# circle_gpio.net
KiCad netlist of a schematic drawn in EAGLE
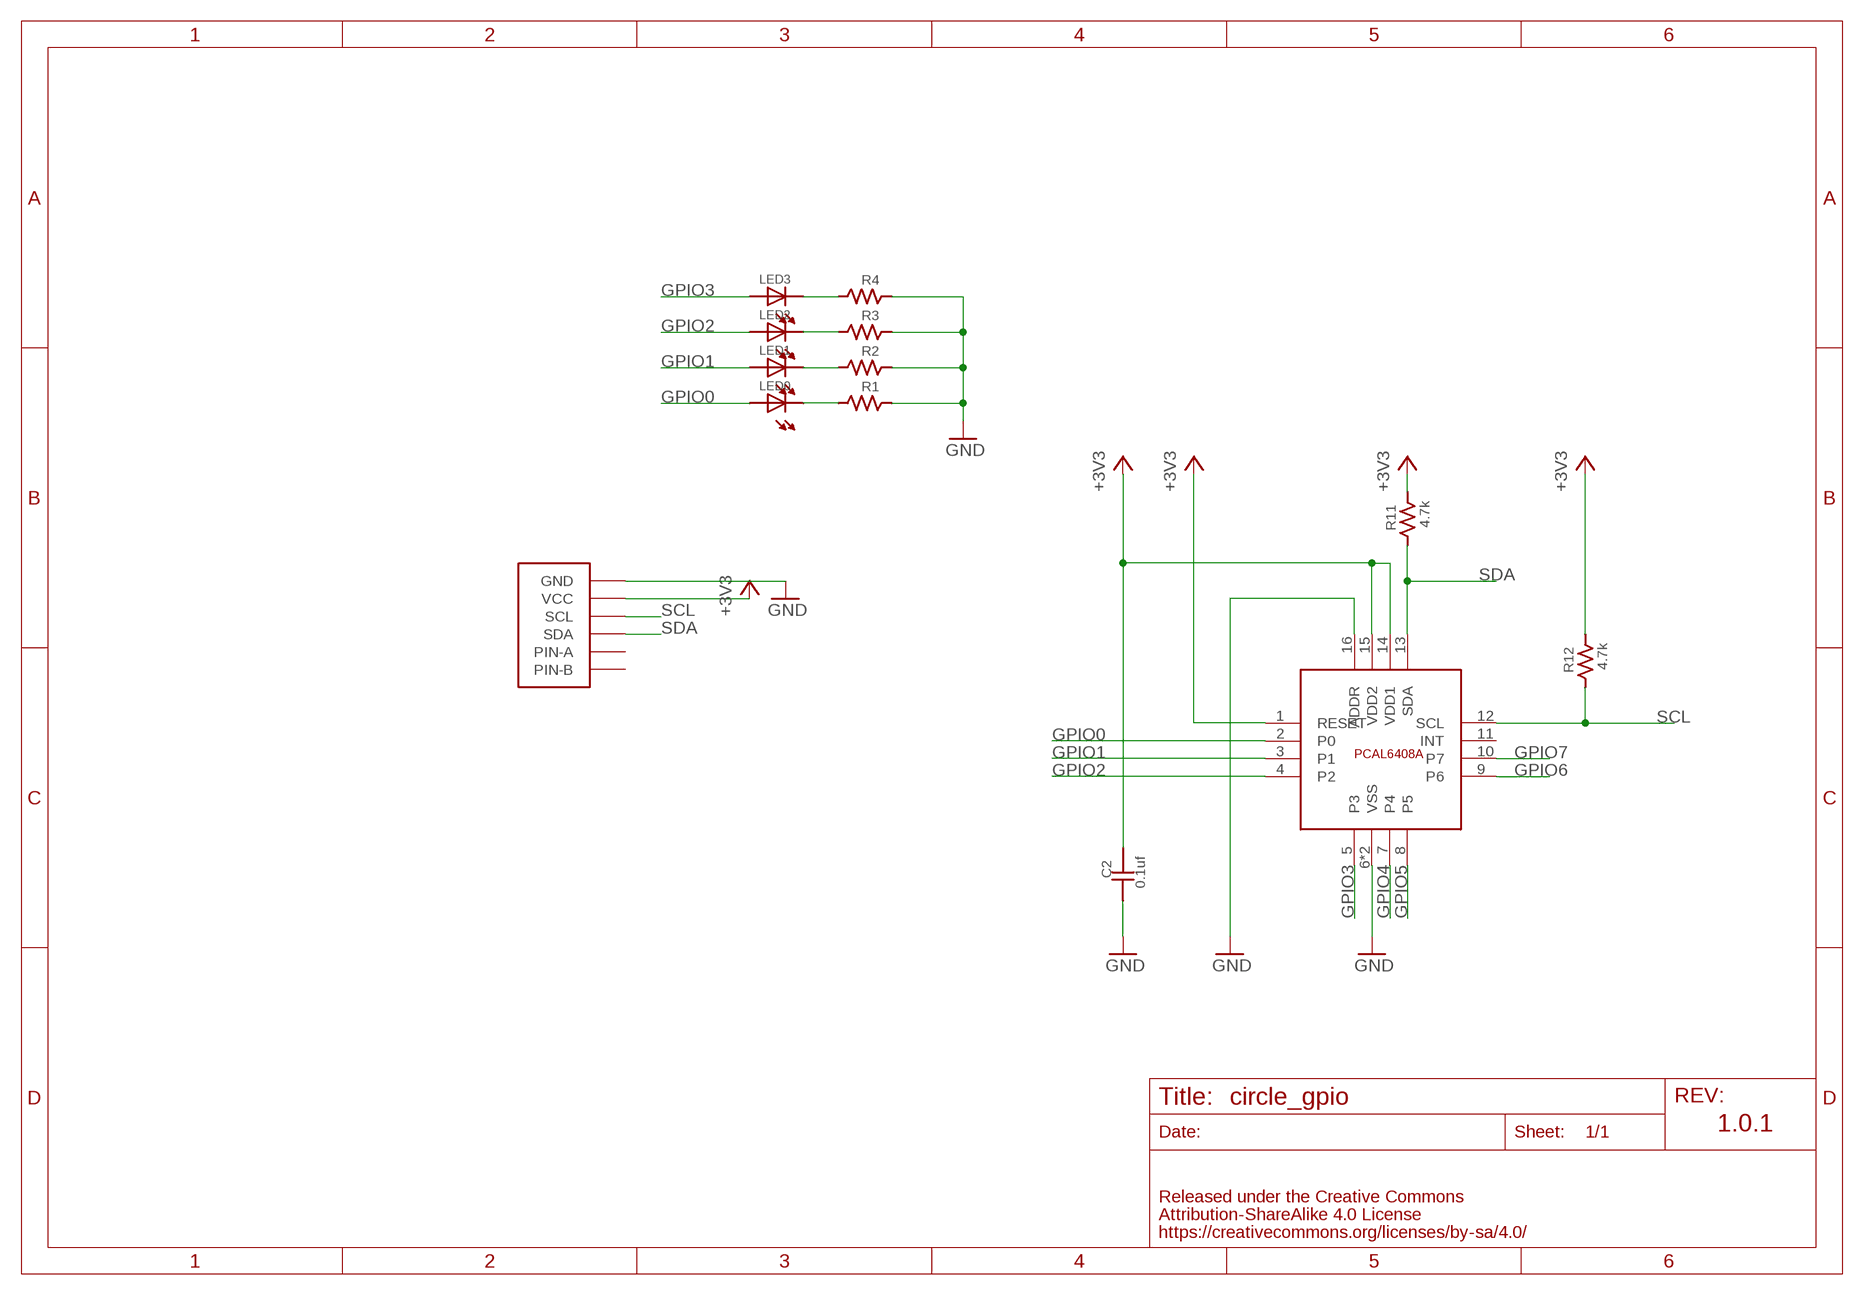
[diagram p0: schematic, sheet 1]

(export (version "E")
  (design (tool "Eeschema 10.0.6"))
  (components
    (comp (ref "C2")
      (value "0.1uf")
      (footprint "eagle-import:0402")
      (libsource (lib "eagle-import") (part "CAPACITOR0402"))
    )
    (comp (ref "LED0")
      (value "LED0402")
      (footprint "eagle-import:0402")
      (libsource (lib "eagle-import") (part "LED0402"))
    )
    (comp (ref "LED1")
      (value "LED0402")
      (footprint "eagle-import:0402")
      (libsource (lib "eagle-import") (part "LED0402"))
    )
    (comp (ref "LED2")
      (value "LED0402")
      (footprint "eagle-import:0402")
      (libsource (lib "eagle-import") (part "LED0402"))
    )
    (comp (ref "LED3")
      (value "LED0402")
      (footprint "eagle-import:0402")
      (libsource (lib "eagle-import") (part "LED0402"))
    )
    (comp (ref "R1")
      (value "RESISTOR-0402")
      (footprint "eagle-import:0402")
      (libsource (lib "eagle-import") (part "RESISTOR-0402"))
    )
    (comp (ref "R2")
      (value "RESISTOR-0402")
      (footprint "eagle-import:0402")
      (libsource (lib "eagle-import") (part "RESISTOR-0402"))
    )
    (comp (ref "R3")
      (value "RESISTOR-0402")
      (footprint "eagle-import:0402")
      (libsource (lib "eagle-import") (part "RESISTOR-0402"))
    )
    (comp (ref "R4")
      (value "RESISTOR-0402")
      (footprint "eagle-import:0402")
      (libsource (lib "eagle-import") (part "RESISTOR-0402"))
    )
    (comp (ref "R11")
      (value "4.7k")
      (footprint "eagle-import:0402")
      (libsource (lib "eagle-import") (part "RESISTOR-0402"))
    )
    (comp (ref "R12")
      (value "4.7k")
      (footprint "eagle-import:0402")
      (libsource (lib "eagle-import") (part "RESISTOR-0402"))
    )
    (comp (ref "U$3")
      (value "FABO-NANO")
      (footprint "eagle-import:FABO-NANO")
      (libsource (lib "eagle-import") (part "FABO-NANO"))
    )
    (comp (ref "U$5")
      (value "NX-PCAL6408A")
      (footprint "eagle-import:NXP-PCAL6408A")
      (libsource (lib "eagle-import") (part "NX-PCAL6408A"))
    )
  )
  (nets
    (net (code "1") (name "+3V3") (class "Default")
      (node (ref "C2") (pin "P$2") (pinfunction "2_P$2") (pintype "passive"))
      (node (ref "R11") (pin "P$2") (pinfunction "2_P$2") (pintype "bidirectional"))
      (node (ref "R12") (pin "P$2") (pinfunction "2_P$2") (pintype "bidirectional"))
      (node (ref "U$3") (pin "VCC") (pinfunction "VCC_VCC") (pintype "bidirectional"))
      (node (ref "U$5") (pin "1") (pinfunction "RESET_1") (pintype "bidirectional"))
      (node (ref "U$5") (pin "14") (pinfunction "VDD1_14") (pintype "bidirectional"))
      (node (ref "U$5") (pin "15") (pinfunction "VDD2_15") (pintype "bidirectional"))
    )
    (net (code "2") (name "/GPIO0") (class "Default")
      (node (ref "LED0") (pin "ANODE") (pinfunction "ANODE_ANODE") (pintype "passive"))
      (node (ref "U$5") (pin "2") (pinfunction "P0_2") (pintype "bidirectional"))
    )
    (net (code "3") (name "/GPIO1") (class "Default")
      (node (ref "LED1") (pin "ANODE") (pinfunction "ANODE_ANODE") (pintype "passive"))
      (node (ref "U$5") (pin "3") (pinfunction "P1_3") (pintype "bidirectional"))
    )
    (net (code "4") (name "/GPIO2") (class "Default")
      (node (ref "LED2") (pin "ANODE") (pinfunction "ANODE_ANODE") (pintype "passive"))
      (node (ref "U$5") (pin "4") (pinfunction "P2_4") (pintype "bidirectional"))
    )
    (net (code "5") (name "/GPIO3") (class "Default")
      (node (ref "LED3") (pin "ANODE") (pinfunction "ANODE_ANODE") (pintype "passive"))
      (node (ref "U$5") (pin "5") (pinfunction "P3_5") (pintype "bidirectional"))
    )
    (net (code "6") (name "/GPIO4") (class "Default")
      (node (ref "U$5") (pin "7") (pinfunction "P4_7") (pintype "bidirectional"))
    )
    (net (code "7") (name "/GPIO5") (class "Default")
      (node (ref "U$5") (pin "8") (pinfunction "P5_8") (pintype "bidirectional"))
    )
    (net (code "8") (name "/GPIO6") (class "Default")
      (node (ref "U$5") (pin "9") (pinfunction "P6_9") (pintype "bidirectional"))
    )
    (net (code "9") (name "/GPIO7") (class "Default")
      (node (ref "U$5") (pin "10") (pinfunction "P7_10") (pintype "bidirectional"))
    )
    (net (code "10") (name "/SCL") (class "Default")
      (node (ref "R12") (pin "P$1") (pinfunction "1_P$1") (pintype "bidirectional"))
      (node (ref "U$3") (pin "0") (pinfunction "SCL_0") (pintype "bidirectional"))
      (node (ref "U$5") (pin "12") (pinfunction "SCL_12") (pintype "bidirectional"))
    )
    (net (code "11") (name "/SDA") (class "Default")
      (node (ref "R11") (pin "P$1") (pinfunction "1_P$1") (pintype "bidirectional"))
      (node (ref "U$3") (pin "1") (pinfunction "SDA_1") (pintype "bidirectional"))
      (node (ref "U$5") (pin "13") (pinfunction "SDA_13") (pintype "bidirectional"))
    )
    (net (code "12") (name "GND") (class "Default")
      (node (ref "C2") (pin "P$1") (pinfunction "1_P$1") (pintype "passive"))
      (node (ref "R1") (pin "P$2") (pinfunction "2_P$2") (pintype "bidirectional"))
      (node (ref "R2") (pin "P$2") (pinfunction "2_P$2") (pintype "bidirectional"))
      (node (ref "R3") (pin "P$2") (pinfunction "2_P$2") (pintype "bidirectional"))
      (node (ref "R4") (pin "P$2") (pinfunction "2_P$2") (pintype "bidirectional"))
      (node (ref "U$3") (pin "GND") (pinfunction "GND_GND") (pintype "bidirectional"))
      (node (ref "U$5") (pin "16") (pinfunction "ADDR_16") (pintype "bidirectional"))
      (node (ref "U$5") (pin "17") (pinfunction "VSS_17") (pintype "bidirectional"))
      (node (ref "U$5") (pin "6") (pinfunction "VSS_6") (pintype "bidirectional"))
    )
    (net (code "13") (name "Net-(R1-1)") (class "Default")
      (node (ref "LED0") (pin "CATHODE") (pinfunction "CATHODE_CATHODE") (pintype "passive"))
      (node (ref "R1") (pin "P$1") (pinfunction "1_P$1") (pintype "bidirectional"))
    )
    (net (code "14") (name "Net-(R2-1)") (class "Default")
      (node (ref "LED1") (pin "CATHODE") (pinfunction "CATHODE_CATHODE") (pintype "passive"))
      (node (ref "R2") (pin "P$1") (pinfunction "1_P$1") (pintype "bidirectional"))
    )
    (net (code "15") (name "Net-(R3-1)") (class "Default")
      (node (ref "LED2") (pin "CATHODE") (pinfunction "CATHODE_CATHODE") (pintype "passive"))
      (node (ref "R3") (pin "P$1") (pinfunction "1_P$1") (pintype "bidirectional"))
    )
    (net (code "16") (name "Net-(R4-1)") (class "Default")
      (node (ref "LED3") (pin "CATHODE") (pinfunction "CATHODE_CATHODE") (pintype "passive"))
      (node (ref "R4") (pin "P$1") (pinfunction "1_P$1") (pintype "bidirectional"))
    )
    (net (code "17") (name "unconnected-(U$3-PIN-A-Pad2)") (class "Default")
      (node (ref "U$3") (pin "2") (pinfunction "PIN-A_2") (pintype "bidirectional"))
    )
    (net (code "18") (name "unconnected-(U$3-PIN-B-Pad3)") (class "Default")
      (node (ref "U$3") (pin "3") (pinfunction "PIN-B_3") (pintype "bidirectional"))
    )
    (net (code "19") (name "unconnected-(U$5-INT-Pad11)") (class "Default")
      (node (ref "U$5") (pin "11") (pinfunction "INT_11") (pintype "bidirectional"))
    )
  )
)
